# RelayPCB1_3_schematic.net
KiCad netlist of a schematic drawn in Altium Designer
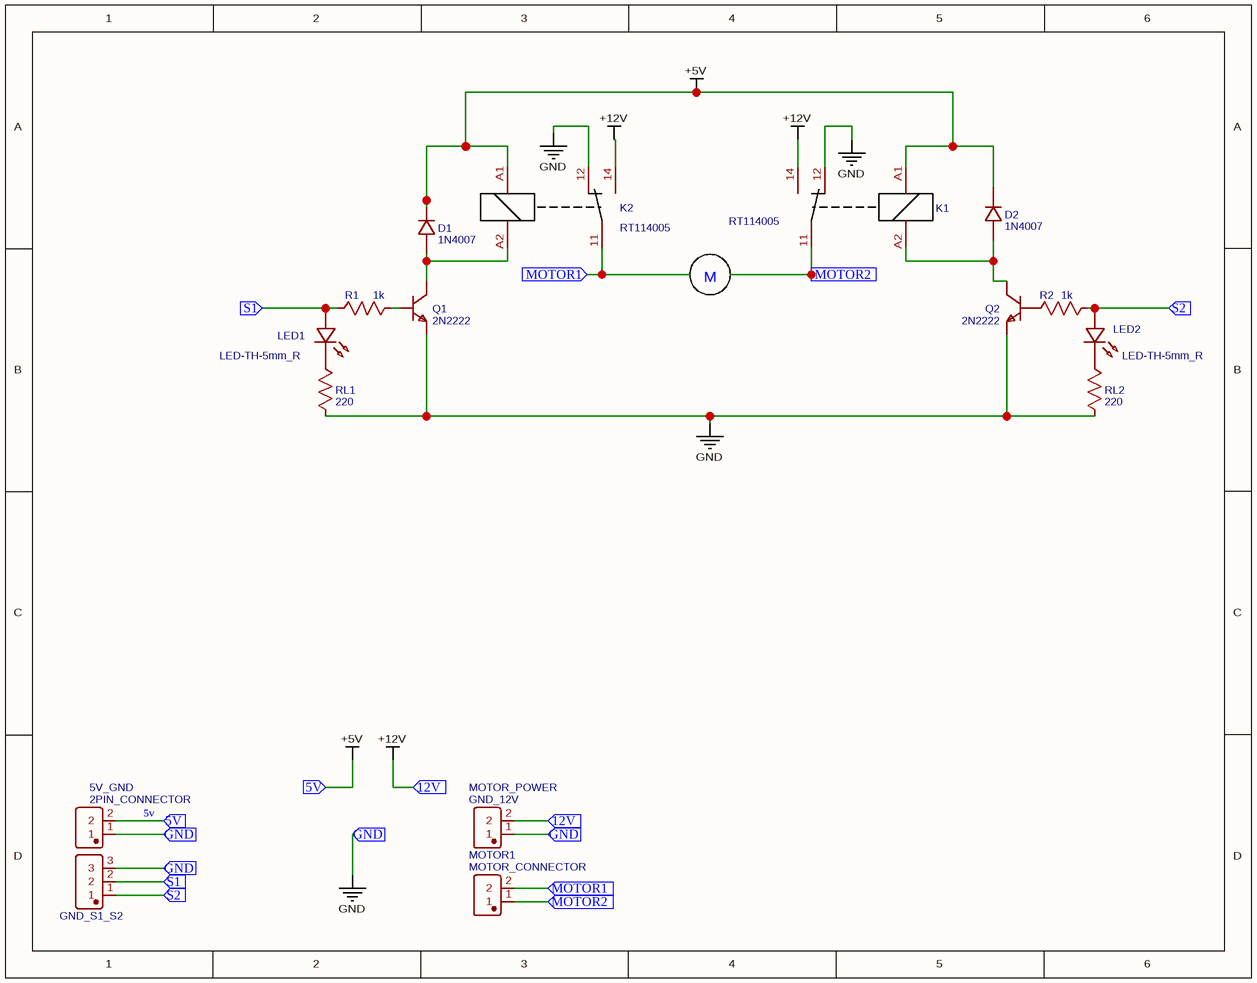
[diagram p0: RelayPCB1.3_schematic.schdoc]

(export (version "E")
  (design (tool "Eeschema 10.0.6"))
  (components
    (comp (ref "5V_GND")
      (value "2PIN_CONNECTOR")
      (fields
        (field (name "MANUFACTURER") "XINLAIYA(新莱亚)")
        (field (name "MANUFACTURER PART") "XY126V-5.0-2P")
        (field (name "CONTRIBUTOR") "LCSC")
      )
      (libsource (lib "altium-import") (part "root_2_2PIN_CONNECTOR_"))
    )
    (comp (ref "D1")
      (value "1N4007")
      (fields (field (name "MANUFACTURER") "SEMTECH") (field (name "CONTRIBUTOR") "LCEDA_Lib"))
      (libsource (lib "altium-import") (part "root_1_1N4007_"))
    )
    (comp (ref "D2")
      (value "1N4007")
      (fields (field (name "MANUFACTURER") "SEMTECH") (field (name "CONTRIBUTOR") "LCEDA_Lib"))
      (libsource (lib "altium-import") (part "root_1_1N4007_"))
    )
    (comp (ref "K1")
      (value "RT114005")
      (fields
        (field (name "MANUFACTURER") "TE")
        (field (name "MANUFACTURER PART") "9-1393239-7")
        (field (name "CONTRIBUTOR") "Michael Fluck")
      )
      (libsource (lib "altium-import") (part "root_2_RT114005_"))
    )
    (comp (ref "K2")
      (value "RT114005")
      (fields
        (field (name "MANUFACTURER") "TE")
        (field (name "MANUFACTURER PART") "9-1393239-7")
        (field (name "CONTRIBUTOR") "Michael Fluck")
      )
      (libsource (lib "altium-import") (part "root_0_RT114005_"))
    )
    (comp (ref "LED1")
      (value "LED-TH-5mm_R")
      (fields
        (field (name "MANUFACTURER") "EVERLIGHT(台湾亿光)")
        (field (name "MANUFACTURER PART") "333-2SURD/S530-A3")
        (field (name "CONTRIBUTOR") "LCEDA_Lib")
      )
      (libsource (lib "altium-import") (part "root_3_LED-TH-5mm_R_"))
    )
    (comp (ref "LED2")
      (value "LED-TH-5mm_R")
      (fields
        (field (name "MANUFACTURER") "EVERLIGHT(台湾亿光)")
        (field (name "MANUFACTURER PART") "333-2SURD/S530-A3")
        (field (name "CONTRIBUTOR") "LCEDA_Lib")
      )
      (libsource (lib "altium-import") (part "root_3_LED-TH-5mm_R_"))
    )
    (comp (ref "MOTOR1")
      (value "MOTOR_CONNECTOR")
      (fields
        (field (name "MANUFACTURER") "XINLAIYA(新莱亚)")
        (field (name "MANUFACTURER PART") "XY126V-5.0-2P")
        (field (name "CONTRIBUTOR") "LCSC")
      )
      (libsource (lib "altium-import") (part "root_2_MOTOR_CONNECTOR_"))
    )
    (comp (ref "MOTOR_POWER")
      (value "GND_12V")
      (fields
        (field (name "MANUFACTURER") "XINLAIYA(新莱亚)")
        (field (name "MANUFACTURER PART") "XY126V-5.0-2P")
        (field (name "CONTRIBUTOR") "LCSC")
      )
      (libsource (lib "altium-import") (part "root_2_GND_12V_"))
    )
    (comp (ref "Q1")
      (value "2N2222")
      (fields
        (field (name "MANUFACTURER") "ST(先科)")
        (field (name "MANUFACTURER PART") "2N2222A")
        (field (name "CONTRIBUTOR") "LCSC")
      )
      (libsource (lib "") (part "root_0_2N2222__1"))
    )
    (comp (ref "Q2")
      (value "2N2222")
      (fields
        (field (name "MANUFACTURER") "ST(先科)")
        (field (name "MANUFACTURER PART") "2N2222A")
        (field (name "CONTRIBUTOR") "LCSC")
      )
      (libsource (lib "altium-import") (part "root_0_2N2222_"))
    )
    (comp (ref "R1")
      (value "1k")
      (fields (field (name "CONTRIBUTOR") "LCEDA_Lib"))
      (libsource (lib "altium-import") (part "root_0_1k_"))
    )
    (comp (ref "R2")
      (value "1k")
      (fields (field (name "CONTRIBUTOR") "LCEDA_Lib"))
      (libsource (lib "altium-import") (part "root_0_1k_"))
    )
    (comp (ref "RL1")
      (value "220")
      (fields (field (name "CONTRIBUTOR") "LCEDA_Lib"))
      (libsource (lib "altium-import") (part "root_1_220_"))
    )
    (comp (ref "RL2")
      (value "220")
      (fields (field (name "CONTRIBUTOR") "LCEDA_Lib"))
      (libsource (lib "altium-import") (part "root_1_220_"))
    )
    (comp (ref "U1")
      (value "GND_S1_S2")
      (fields
        (field (name "MANUFACTURER") "XINLAIYA(新莱亚)")
        (field (name "MANUFACTURER PART") "XY126V-5.0-3P")
        (field (name "CONTRIBUTOR") "LCSC")
      )
      (libsource (lib "altium-import") (part "root_2_GND_S1_S2_"))
    )
  )
  (nets
    (net (code "1") (name "+5V") (class "Default")
      (node (ref "5V_GND") (pin "2") (pinfunction "2_2") (pintype "passive"))
      (node (ref "D1") (pin "1") (pinfunction "1_1") (pintype "passive"))
      (node (ref "D2") (pin "1") (pinfunction "1_1") (pintype "passive"))
      (node (ref "K1") (pin "A1") (pinfunction "A1_A1") (pintype "passive"))
      (node (ref "K2") (pin "A1") (pinfunction "A1_A1") (pintype "passive"))
    )
    (net (code "2") (name "+12V") (class "Default")
      (node (ref "K1") (pin "14") (pinfunction "A6_14") (pintype "passive"))
      (node (ref "K2") (pin "14") (pinfunction "A6_14") (pintype "passive"))
      (node (ref "MOTOR_POWER") (pin "2") (pinfunction "2_2") (pintype "passive"))
    )
    (net (code "3") (name "/MOTOR1") (class "Default")
      (node (ref "K2") (pin "11") (pinfunction "11_11") (pintype "passive"))
      (node (ref "MOTOR1") (pin "2") (pinfunction "2_2") (pintype "passive"))
    )
    (net (code "4") (name "/MOTOR2") (class "Default")
      (node (ref "K1") (pin "11") (pinfunction "11_11") (pintype "passive"))
      (node (ref "MOTOR1") (pin "1") (pinfunction "1_1") (pintype "passive"))
    )
    (net (code "5") (name "/S1") (class "Default")
      (node (ref "LED1") (pin "1") (pinfunction "1_1") (pintype "passive"))
      (node (ref "R1") (pin "1") (pinfunction "1_1") (pintype "passive"))
      (node (ref "U1") (pin "2") (pinfunction "2_2") (pintype "passive"))
    )
    (net (code "6") (name "/S2") (class "Default")
      (node (ref "LED2") (pin "1") (pinfunction "1_1") (pintype "passive"))
      (node (ref "R2") (pin "2") (pinfunction "2_2") (pintype "passive"))
      (node (ref "U1") (pin "1") (pinfunction "1_1") (pintype "passive"))
    )
    (net (code "7") (name "GND") (class "Default")
      (node (ref "5V_GND") (pin "1") (pinfunction "1_1") (pintype "passive"))
      (node (ref "K1") (pin "12") (pinfunction "A5_12") (pintype "passive"))
      (node (ref "K2") (pin "12") (pinfunction "A5_12") (pintype "passive"))
      (node (ref "MOTOR_POWER") (pin "1") (pinfunction "1_1") (pintype "passive"))
      (node (ref "Q1") (pin "1") (pinfunction "E_1") (pintype "passive"))
      (node (ref "Q2") (pin "1") (pinfunction "E_1") (pintype "passive"))
      (node (ref "RL1") (pin "1") (pinfunction "1_1") (pintype "passive"))
      (node (ref "RL2") (pin "1") (pinfunction "1_1") (pintype "passive"))
      (node (ref "U1") (pin "3") (pinfunction "3_3") (pintype "passive"))
    )
    (net (code "8") (name "Net-(LED1-Pad2)") (class "Default")
      (node (ref "LED1") (pin "2") (pinfunction "2_2") (pintype "passive"))
      (node (ref "RL1") (pin "2") (pinfunction "2_2") (pintype "passive"))
    )
    (net (code "9") (name "Net-(LED2-Pad2)") (class "Default")
      (node (ref "LED2") (pin "2") (pinfunction "2_2") (pintype "passive"))
      (node (ref "RL2") (pin "2") (pinfunction "2_2") (pintype "passive"))
    )
    (net (code "10") (name "Net-(Q1-B)") (class "Default")
      (node (ref "Q1") (pin "2") (pinfunction "B_2") (pintype "passive"))
      (node (ref "R1") (pin "2") (pinfunction "2_2") (pintype "passive"))
    )
    (net (code "11") (name "Net-(Q1-C)") (class "Default")
      (node (ref "D1") (pin "2") (pinfunction "2_2") (pintype "passive"))
      (node (ref "K2") (pin "A2") (pinfunction "A2_A2") (pintype "passive"))
      (node (ref "Q1") (pin "3") (pinfunction "C_3") (pintype "passive"))
    )
    (net (code "12") (name "Net-(Q2-B)") (class "Default")
      (node (ref "Q2") (pin "2") (pinfunction "B_2") (pintype "passive"))
      (node (ref "R2") (pin "1") (pinfunction "1_1") (pintype "passive"))
    )
    (net (code "13") (name "Net-(Q2-C)") (class "Default")
      (node (ref "D2") (pin "2") (pinfunction "2_2") (pintype "passive"))
      (node (ref "K1") (pin "A2") (pinfunction "A2_A2") (pintype "passive"))
      (node (ref "Q2") (pin "3") (pinfunction "C_3") (pintype "passive"))
    )
  )
)
